# Power_Supply.net
KiCad netlist of a schematic drawn in Altium Designer
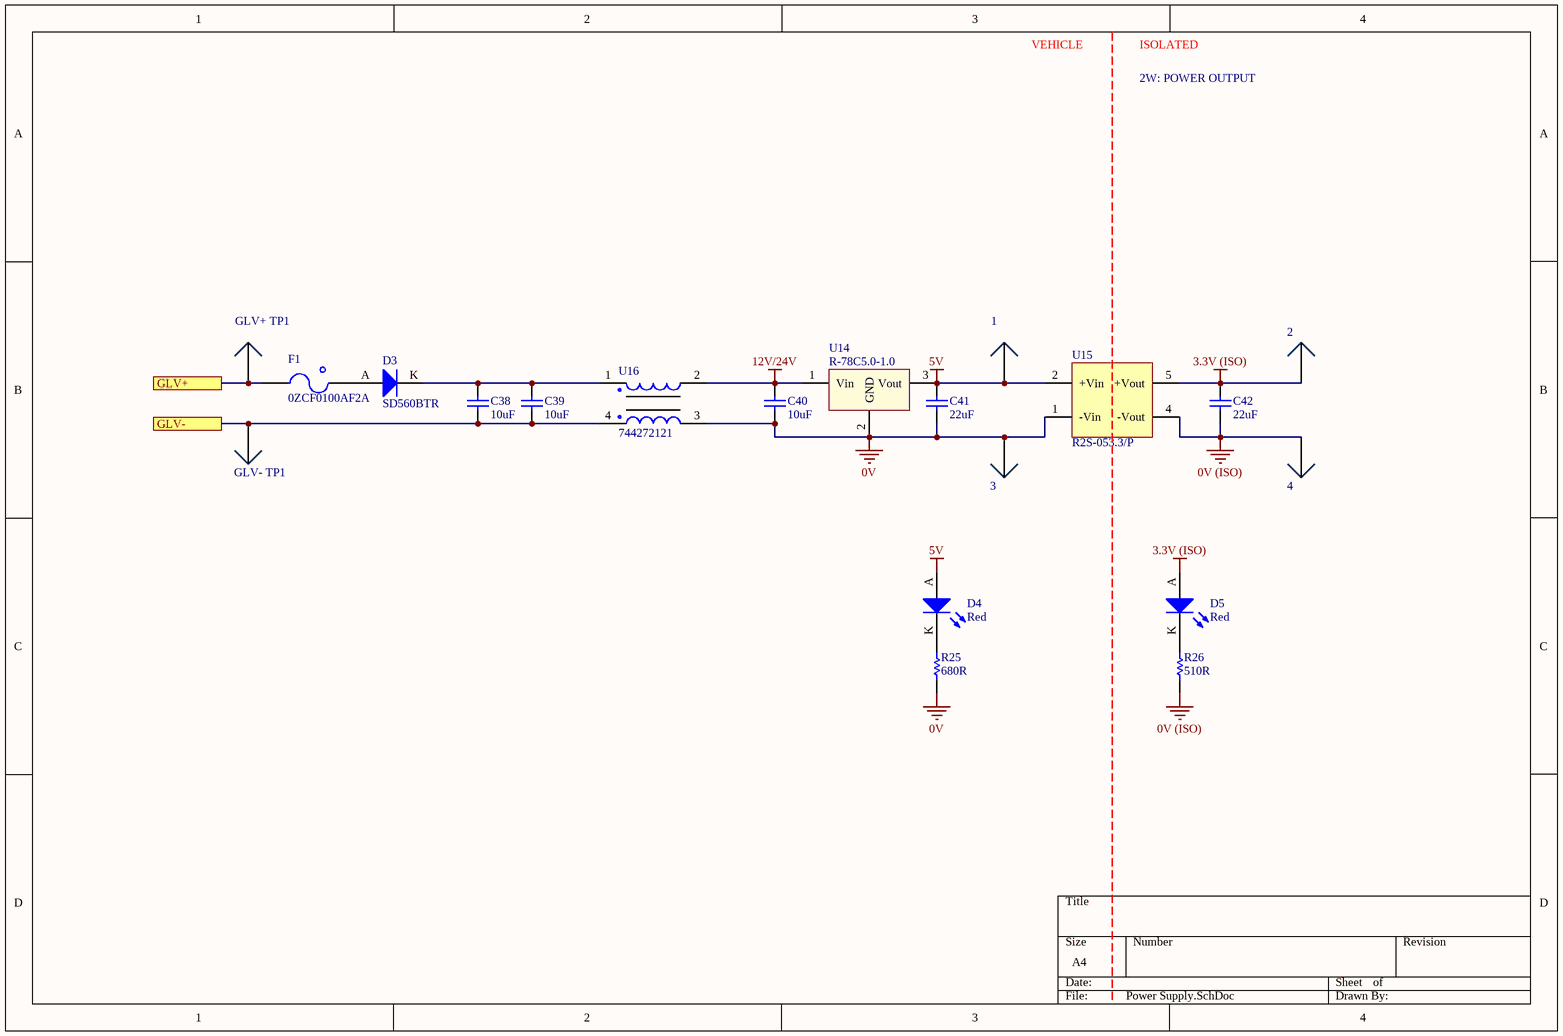
[diagram p0: Power Supply.SchDoc]

(export (version "E")
  (design (tool "Eeschema 10.0.6"))
  (components
    (comp (ref "1")
      (value "0mm")
      (footprint "SMD Test Point")
      (fields (field (name "PART NUMBER") "SMD Test Point") (field (name "CONTACT") "NA"))
      (libsource (lib "ts_20-standard-connectors") (part "Test Point"))
    )
    (comp (ref "2")
      (value "0mm")
      (footprint "SMD Test Point")
      (fields (field (name "PART NUMBER") "SMD Test Point") (field (name "CONTACT") "NA"))
      (libsource (lib "ts_20-standard-connectors") (part "Test Point"))
    )
    (comp (ref "3")
      (value "0mm")
      (footprint "SMD Test Point")
      (fields (field (name "PART NUMBER") "SMD Test Point") (field (name "CONTACT") "NA"))
      (libsource (lib "ts_20-standard-connectors") (part "Test Point"))
    )
    (comp (ref "4")
      (value "0mm")
      (footprint "SMD Test Point")
      (fields (field (name "PART NUMBER") "SMD Test Point") (field (name "CONTACT") "NA"))
      (libsource (lib "ts_20-standard-connectors") (part "Test Point"))
    )
    (comp (ref "C38")
      (value "10uF")
      (footprint "0805")
      (fields
        (field (name "PART NUMBER") "GRM21BR6YA106KE43L")
        (field (name "TOLERANCE") "10%")
        (field (name "MANUFACTURER") "muRata")
      )
      (libsource (lib "ts_20-standard-library") (part "Capacitor"))
    )
    (comp (ref "C39")
      (value "10uF")
      (footprint "0805")
      (fields
        (field (name "PART NUMBER") "GRM21BR6YA106KE43L")
        (field (name "TOLERANCE") "10%")
        (field (name "MANUFACTURER") "muRata")
      )
      (libsource (lib "ts_20-standard-library") (part "Capacitor"))
    )
    (comp (ref "C40")
      (value "10uF")
      (footprint "0805")
      (fields
        (field (name "PART NUMBER") "GRM21BR6YA106KE43L")
        (field (name "TOLERANCE") "10%")
        (field (name "MANUFACTURER") "muRata")
      )
      (libsource (lib "ts_20-standard-library") (part "Capacitor"))
    )
    (comp (ref "C41")
      (value "22uF")
      (footprint "1206")
      (fields
        (field (name "PART NUMBER") "CC1206MKX5R7BB226")
        (field (name "TOLERANCE") "20%")
        (field (name "MANUFACTURER") "YAGEO")
      )
      (libsource (lib "ts_20-standard-library") (part "Capacitor"))
    )
    (comp (ref "C42")
      (value "22uF")
      (footprint "1206")
      (fields
        (field (name "PART NUMBER") "CC1206MKX5R7BB226")
        (field (name "TOLERANCE") "20%")
        (field (name "MANUFACTURER") "YAGEO")
      )
      (libsource (lib "ts_20-standard-library") (part "Capacitor"))
    )
    (comp (ref "D3")
      (value "SD560BTR")
      (footprint "SMB Diode")
      (description "1.2V_F 600V 5A SMB")
      (fields
        (field (name "MANUFACTURER") "SMC Diode Solutions")
        (field (name "DIGIKEY PART NUMBER") "1655-1530-2-ND")
      )
      (libsource (lib "ts_20-standard-library") (part "Diode"))
    )
    (comp (ref "D4")
      (value "Red")
      (footprint "0805 LED")
      (description "Red LED Indication - Discrete 1.75V 0805 (2012 Metric)")
      (fields (field (name "PART NUMBER") "SML-210LTT86") (field (name "MANUFACTURER") "ROHM Semiconductor"))
      (libsource (lib "ts_20-standard-library") (part "LED"))
    )
    (comp (ref "D5")
      (value "Red")
      (footprint "0805 LED")
      (description "Red LED Indication - Discrete 1.75V 0805 (2012 Metric)")
      (fields (field (name "PART NUMBER") "SML-210LTT86") (field (name "MANUFACTURER") "ROHM Semiconductor"))
      (libsource (lib "ts_20-standard-library") (part "LED"))
    )
    (comp (ref "F1")
      (value "0ZCF0100AF2A")
      (footprint "2920")
      (description "PTC RESET FUSE 60V 1A 292")
      (fields
        (field (name "MANUFACTURER") "Littelfuse Inc.")
        (field (name "DIGIKEY PART NUMBER") "507-2070-1-ND")
      )
      (libsource (lib "ts_20-standard-library") (part "PTC Fuse"))
    )
    (comp (ref "GLV+ TP1")
      (value "0mm")
      (footprint "SMD Test Point")
      (fields (field (name "PART NUMBER") "SMD Test Point") (field (name "CONTACT") "NA"))
      (libsource (lib "ts_20-standard-connectors") (part "Test Point"))
    )
    (comp (ref "GLV- TP1")
      (value "0mm")
      (footprint "SMD Test Point")
      (fields (field (name "PART NUMBER") "SMD Test Point") (field (name "CONTACT") "NA"))
      (libsource (lib "ts_20-standard-connectors") (part "Test Point"))
    )
    (comp (ref "R25")
      (value "680R")
      (footprint "0805")
      (fields
        (field (name "PART NUMBER") "RC0805FR07680RL")
        (field (name "MANUFACTURER") "YAGEO")
        (field (name "TOLERANCE") "0.01")
      )
      (libsource (lib "ts_20-standard-library") (part "Resistor"))
    )
    (comp (ref "R26")
      (value "510R")
      (footprint "0805")
      (fields
        (field (name "PART NUMBER") "RC0805FR07510RL")
        (field (name "MANUFACTURER") "YAGEO")
        (field (name "TOLERANCE") "0.01")
      )
      (libsource (lib "ts_20-standard-library") (part "Resistor"))
    )
    (comp (ref "U14")
      (value "R-78C5.0-1.0")
      (footprint "RECOM 3-SIP")
      (description "CONV DC/DC 1A 5V OUT SIP VERT")
      (fields (field (name "MANUFACTURER") "Recom") (field (name "DIGIKEY PART NUMBER") "945-1395-5-ND"))
      (libsource (lib "ts_20-standard-library") (part "R-78C5.0-1.0"))
    )
    (comp (ref "U15")
      (value "R2S-053.3/P")
      (footprint "RECOM 8-SMD (5 Pin)")
      (description "Isolated Module DC DC Converter 1 Output 3.3V 606mA 4.5V - 5.5V Input")
      (fields (field (name "MANUFACTURER") "Recom") (field (name "DIGIKEY PART NUMBER") "945-2677-5-ND"))
      (libsource (lib "ts_20-standard-library") (part "R2S-053.3/P"))
    )
    (comp (ref "U16")
      (value "744272121")
      (footprint "Wurth 4-PC Pad")
      (description "120µH @ 100kHz 2 Line Common Mode Choke Surface Mount 460 Ohms @ 30MHz 2.5A DCR 25mOhm")
      (fields
        (field (name "MANUFACTURER") "Wurth Electronics Inc")
        (field (name "DIGIKEY PART NUMBER") "732-1489-1-ND")
      )
      (libsource (lib "ts_20-standard-library") (part "744272121"))
    )
  )
  (nets
    (net (code "1") (name "/GLV+") (class "Default")
      (node (ref "F1") (pin "1") (pinfunction "1_1") (pintype "passive"))
      (node (ref "GLV+ TP1") (pin "1") (pinfunction "1_1") (pintype "passive"))
    )
    (net (code "2") (name "/GLV-") (class "Default")
      (node (ref "C38") (pin "1") (pinfunction "1_1") (pintype "passive"))
      (node (ref "C39") (pin "1") (pinfunction "1_1") (pintype "passive"))
      (node (ref "GLV- TP1") (pin "1") (pinfunction "1_1") (pintype "passive"))
      (node (ref "U16") (pin "4") (pinfunction "4_4") (pintype "passive"))
    )
    (net (code "3") (name "0V") (class "Default")
      (node (ref "3") (pin "1") (pinfunction "1_1") (pintype "passive"))
      (node (ref "C40") (pin "1") (pinfunction "1_1") (pintype "passive"))
      (node (ref "C41") (pin "1") (pinfunction "1_1") (pintype "passive"))
      (node (ref "R25") (pin "1") (pinfunction "1_1") (pintype "passive"))
      (node (ref "U14") (pin "2") (pinfunction "GND_2") (pintype "passive"))
      (node (ref "U15") (pin "1") (pinfunction "-Vin_1") (pintype "power_in"))
      (node (ref "U16") (pin "3") (pinfunction "3_3") (pintype "power_in"))
    )
    (net (code "4") (name "0V (ISO)") (class "Default")
      (node (ref "4") (pin "1") (pinfunction "1_1") (pintype "passive"))
      (node (ref "C42") (pin "1") (pinfunction "1_1") (pintype "passive"))
      (node (ref "R26") (pin "1") (pinfunction "1_1") (pintype "passive"))
      (node (ref "U15") (pin "4") (pinfunction "-Vout_4") (pintype "power_in"))
    )
    (net (code "5") (name "3.3V (ISO)") (class "Default")
      (node (ref "2") (pin "1") (pinfunction "1_1") (pintype "passive"))
      (node (ref "C42") (pin "2") (pinfunction "2_2") (pintype "passive"))
      (node (ref "D5") (pin "A") (pinfunction "A_A") (pintype "passive"))
      (node (ref "U15") (pin "5") (pinfunction "+Vout_5") (pintype "power_in"))
    )
    (net (code "6") (name "5V") (class "Default")
      (node (ref "1") (pin "1") (pinfunction "1_1") (pintype "passive"))
      (node (ref "C41") (pin "2") (pinfunction "2_2") (pintype "passive"))
      (node (ref "D4") (pin "A") (pinfunction "A_A") (pintype "passive"))
      (node (ref "U14") (pin "3") (pinfunction "Vout_3") (pintype "passive"))
      (node (ref "U15") (pin "2") (pinfunction "+Vin_2") (pintype "power_in"))
    )
    (net (code "7") (name "12V{slash}24V") (class "Default")
      (node (ref "C40") (pin "2") (pinfunction "2_2") (pintype "passive"))
      (node (ref "U14") (pin "1") (pinfunction "Vin_1") (pintype "passive"))
      (node (ref "U16") (pin "2") (pinfunction "2_2") (pintype "passive"))
    )
    (net (code "8") (name "Net-(C38-Pad2)") (class "Default")
      (node (ref "C38") (pin "2") (pinfunction "2_2") (pintype "passive"))
      (node (ref "C39") (pin "2") (pinfunction "2_2") (pintype "passive"))
      (node (ref "D3") (pin "K") (pinfunction "K_K") (pintype "passive"))
      (node (ref "U16") (pin "1") (pinfunction "1_1") (pintype "passive"))
    )
    (net (code "9") (name "Net-(D3-PadA)") (class "Default")
      (node (ref "D3") (pin "A") (pinfunction "A_A") (pintype "passive"))
      (node (ref "F1") (pin "2") (pinfunction "2_2") (pintype "passive"))
    )
    (net (code "10") (name "Net-(D4-PadK)") (class "Default")
      (node (ref "D4") (pin "K") (pinfunction "K_K") (pintype "passive"))
      (node (ref "R25") (pin "2") (pinfunction "2_2") (pintype "passive"))
    )
    (net (code "11") (name "Net-(D5-PadK)") (class "Default")
      (node (ref "D5") (pin "K") (pinfunction "K_K") (pintype "passive"))
      (node (ref "R26") (pin "2") (pinfunction "2_2") (pintype "passive"))
    )
  )
)
